# USB_C.net
KiCad netlist of a schematic drawn in Altium Designer
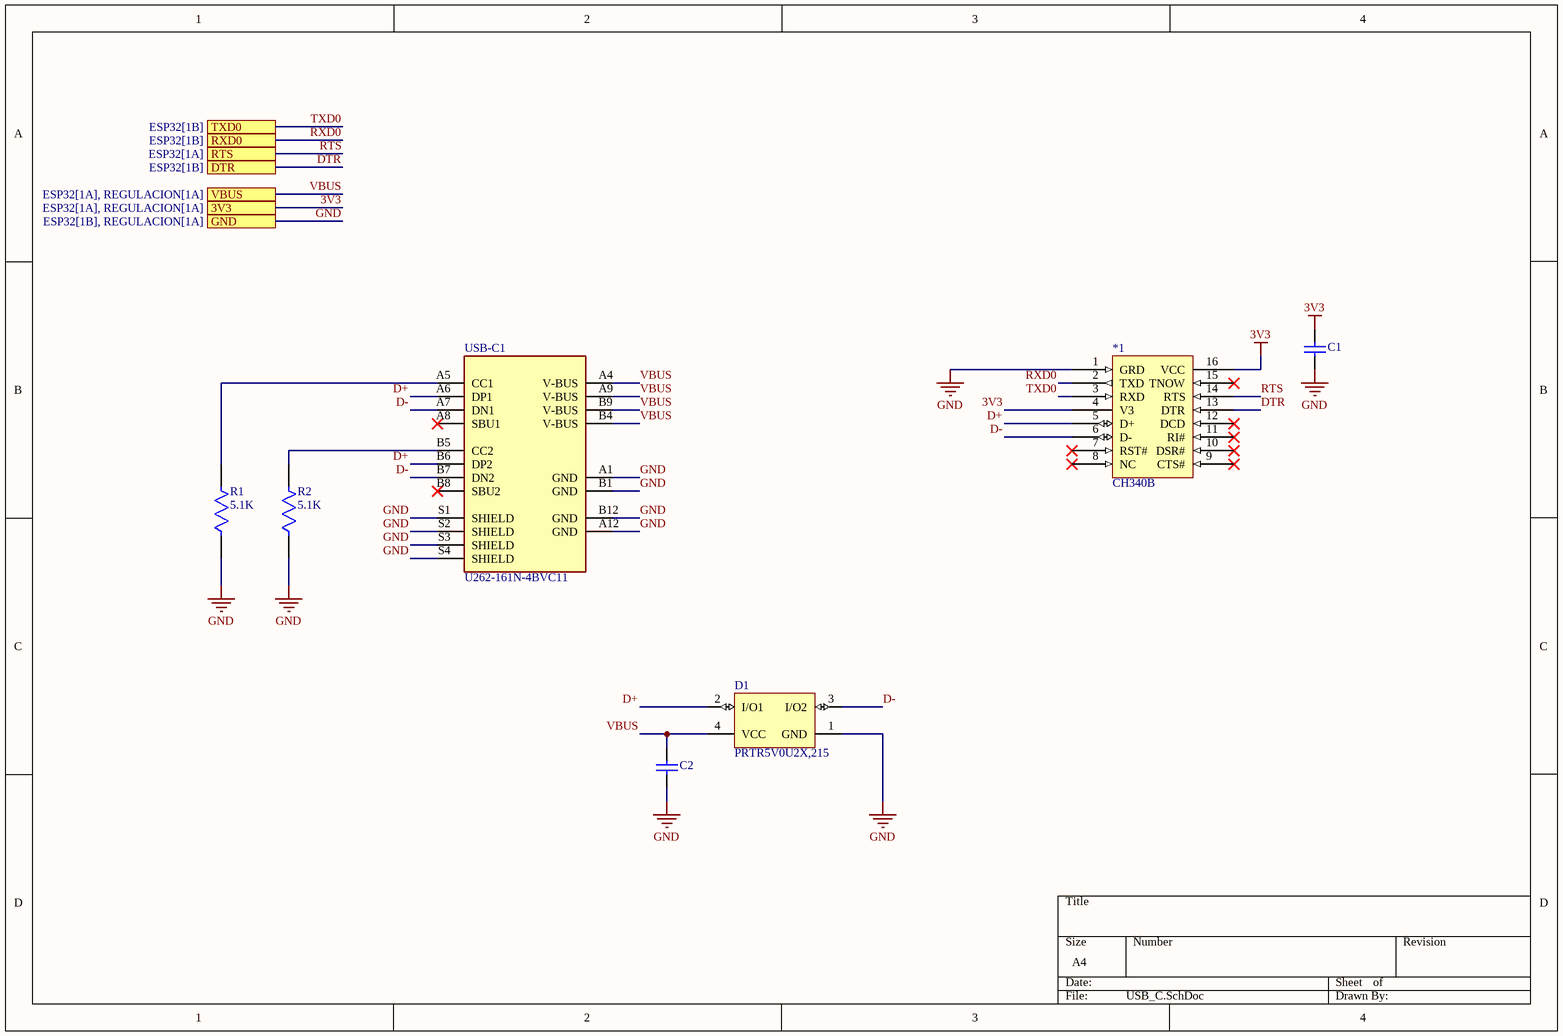
[diagram p0: USB_C.SchDoc]

(export (version "E")
  (design (tool "Eeschema 10.0.6"))
  (components
    (comp (ref "*1")
      (value "CH340B")
      (footprint "CH340B")
      (description "- USB 2.0 Transceiver 2Mbps SOP-16_150mil USB ICs ROHS")
      (libsource (lib "Isidro_Library") (part "CH340B"))
    )
    (comp (ref "C1")
      (value "08055C104KAT2A")
      (footprint "CAPC2013X94X50ML20T25")
      (description "Chip Capacitor, Ceramic, 0.1 uF, 10%, 50 V, 0805, RoHS, Tape and Reel")
      (fields (field (name "MANUFACTURER") "AVX"))
      (libsource (lib "Altium Content Vault") (part "CAP-NP-2"))
    )
    (comp (ref "C2")
      (value "08055C104KAT2A")
      (footprint "CAPC2013X94X50ML20T25")
      (description "Chip Capacitor, Ceramic, 0.1 uF, 10%, 50 V, 0805, RoHS, Tape and Reel")
      (fields (field (name "MANUFACTURER") "AVX"))
      (libsource (lib "Altium Content Vault") (part "CAP-NP-2"))
    )
    (comp (ref "D1")
      (value "PRTR5V0U2X,215")
      (footprint "NXP-SOT143B-4_V")
      (fields (field (name "MANUFACTURER") "NXP Semiconductors"))
      (libsource (lib "Altium Content Vault") (part "NXP-PRTR5V0U2X,215-4"))
    )
    (comp (ref "R1")
      (value "5.1K")
      (footprint "FP-CRCW0805-e3-IPC_A")
      (description "RES Thick Film, 5.1kΩ, 1%, 0.125W, 100ppm/°C, 0805")
      (fields (field (name "TOLERANCE") "1%"))
      (libsource (lib "Altium Content Vault") (part "1029c3af85768c4190bb7ad29bc67b5"))
    )
    (comp (ref "R2")
      (value "5.1K")
      (footprint "FP-CRCW0805-e3-IPC_A")
      (description "RES Thick Film, 5.1kΩ, 1%, 0.125W, 100ppm/°C, 0805")
      (fields (field (name "TOLERANCE") "1%"))
      (libsource (lib "Altium Content Vault") (part "1029c3af85768c4190bb7ad29bc67b5"))
    )
    (comp (ref "USB-C1")
      (value "U262-161N-4BVC11")
      (footprint "U262-161N-4BVC11")
      (description "USB - Type C Female 16 SMT USB Connectors RoHS")
      (libsource (lib "AQIMon") (part "U262-161N-4BVC11"))
    )
  )
  (nets
    (net (code "1") (name "/D+") (class "Default")
      (node (ref "*1") (pin "5") (pinfunction "D+_5") (pintype "bidirectional"))
      (node (ref "D1") (pin "2") (pinfunction "I/O1_2") (pintype "bidirectional"))
      (node (ref "USB-C1") (pin "A6") (pinfunction "DP1_A6") (pintype "power_in"))
      (node (ref "USB-C1") (pin "B6") (pinfunction "DP2_B6") (pintype "power_in"))
    )
    (net (code "2") (name "/D-") (class "Default")
      (node (ref "*1") (pin "6") (pinfunction "D-_6") (pintype "bidirectional"))
      (node (ref "D1") (pin "3") (pinfunction "I/O2_3") (pintype "bidirectional"))
      (node (ref "USB-C1") (pin "A7") (pinfunction "DN1_A7") (pintype "power_in"))
      (node (ref "USB-C1") (pin "B7") (pinfunction "DN2_B7") (pintype "power_in"))
    )
    (net (code "3") (name "/DTR") (class "Default")
      (node (ref "*1") (pin "13") (pinfunction "DTR_13") (pintype "input"))
    )
    (net (code "4") (name "/RTS") (class "Default")
      (node (ref "*1") (pin "14") (pinfunction "RTS_14") (pintype "input"))
    )
    (net (code "5") (name "/RXD0") (class "Default")
      (node (ref "*1") (pin "2") (pinfunction "TXD_2") (pintype "output"))
    )
    (net (code "6") (name "/TXD0") (class "Default")
      (node (ref "*1") (pin "3") (pinfunction "RXD_3") (pintype "input"))
    )
    (net (code "7") (name "/VBUS") (class "Default")
      (node (ref "C2") (pin "2") (pinfunction "2_2") (pintype "passive"))
      (node (ref "D1") (pin "4") (pinfunction "VCC_4") (pintype "power_in"))
      (node (ref "USB-C1") (pin "A4") (pinfunction "V-BUS_A4") (pintype "power_in"))
      (node (ref "USB-C1") (pin "A9") (pinfunction "V-BUS_A9") (pintype "power_in"))
      (node (ref "USB-C1") (pin "B4") (pinfunction "V-BUS_B4") (pintype "power_in"))
      (node (ref "USB-C1") (pin "B9") (pinfunction "V-BUS_B9") (pintype "power_in"))
    )
    (net (code "8") (name "3V3") (class "Default")
      (node (ref "*1") (pin "16") (pinfunction "VCC_16") (pintype "power_in"))
      (node (ref "*1") (pin "4") (pinfunction "V3_4") (pintype "power_in"))
      (node (ref "C1") (pin "2") (pinfunction "2_2") (pintype "passive"))
    )
    (net (code "9") (name "GND") (class "Default")
      (node (ref "*1") (pin "1") (pinfunction "GRD_1") (pintype "input"))
      (node (ref "C1") (pin "1") (pinfunction "1_1") (pintype "passive"))
      (node (ref "C2") (pin "1") (pinfunction "1_1") (pintype "passive"))
      (node (ref "D1") (pin "1") (pinfunction "GND_1") (pintype "power_in"))
      (node (ref "R1") (pin "1") (pinfunction "1_1") (pintype "passive"))
      (node (ref "R2") (pin "1") (pinfunction "1_1") (pintype "passive"))
      (node (ref "USB-C1") (pin "A1") (pinfunction "GND_A1") (pintype "power_in"))
      (node (ref "USB-C1") (pin "A12") (pinfunction "GND_A12") (pintype "power_in"))
      (node (ref "USB-C1") (pin "B1") (pinfunction "GND_B1") (pintype "power_in"))
      (node (ref "USB-C1") (pin "B12") (pinfunction "GND_B12") (pintype "power_in"))
      (node (ref "USB-C1") (pin "S1") (pinfunction "SHIELD_S1") (pintype "passive"))
      (node (ref "USB-C1") (pin "S2") (pinfunction "SHIELD_S2") (pintype "passive"))
      (node (ref "USB-C1") (pin "S3") (pinfunction "SHIELD_S3") (pintype "passive"))
      (node (ref "USB-C1") (pin "S4") (pinfunction "SHIELD_S4") (pintype "passive"))
    )
    (net (code "10") (name "Net-(USB-C1-CC1)") (class "Default")
      (node (ref "R1") (pin "2") (pinfunction "2_2") (pintype "passive"))
      (node (ref "USB-C1") (pin "A5") (pinfunction "CC1_A5") (pintype "power_in"))
    )
    (net (code "11") (name "Net-(USB-C1-CC2)") (class "Default")
      (node (ref "R2") (pin "2") (pinfunction "2_2") (pintype "passive"))
      (node (ref "USB-C1") (pin "B5") (pinfunction "CC2_B5") (pintype "power_in"))
    )
    (net (code "12") (name "unconnected-(*1-CTS#-Pad9)") (class "Default")
      (node (ref "*1") (pin "9") (pinfunction "CTS#_9") (pintype "input+no_connect"))
    )
    (net (code "13") (name "unconnected-(*1-DCD-Pad12)") (class "Default")
      (node (ref "*1") (pin "12") (pinfunction "DCD_12") (pintype "input+no_connect"))
    )
    (net (code "14") (name "unconnected-(*1-DSR#-Pad10)") (class "Default")
      (node (ref "*1") (pin "10") (pinfunction "DSR#_10") (pintype "input+no_connect"))
    )
    (net (code "15") (name "unconnected-(*1-NC-Pad8)") (class "Default")
      (node (ref "*1") (pin "8") (pinfunction "NC_8") (pintype "input+no_connect"))
    )
    (net (code "16") (name "unconnected-(*1-RI#-Pad11)") (class "Default")
      (node (ref "*1") (pin "11") (pinfunction "RI#_11") (pintype "input+no_connect"))
    )
    (net (code "17") (name "unconnected-(*1-RST#-Pad7)") (class "Default")
      (node (ref "*1") (pin "7") (pinfunction "RST#_7") (pintype "input+no_connect"))
    )
    (net (code "18") (name "unconnected-(*1-TNOW-Pad15)") (class "Default")
      (node (ref "*1") (pin "15") (pinfunction "TNOW_15") (pintype "input+no_connect"))
    )
    (net (code "19") (name "unconnected-(USB-C1-SBU1-PadA8)") (class "Default")
      (node (ref "USB-C1") (pin "A8") (pinfunction "SBU1_A8") (pintype "power_in+no_connect"))
    )
    (net (code "20") (name "unconnected-(USB-C1-SBU2-PadB8)") (class "Default")
      (node (ref "USB-C1") (pin "B8") (pinfunction "SBU2_B8") (pintype "power_in+no_connect"))
    )
  )
)
